# Phaser_Board.net
KiCad netlist of a schematic drawn in EAGLE
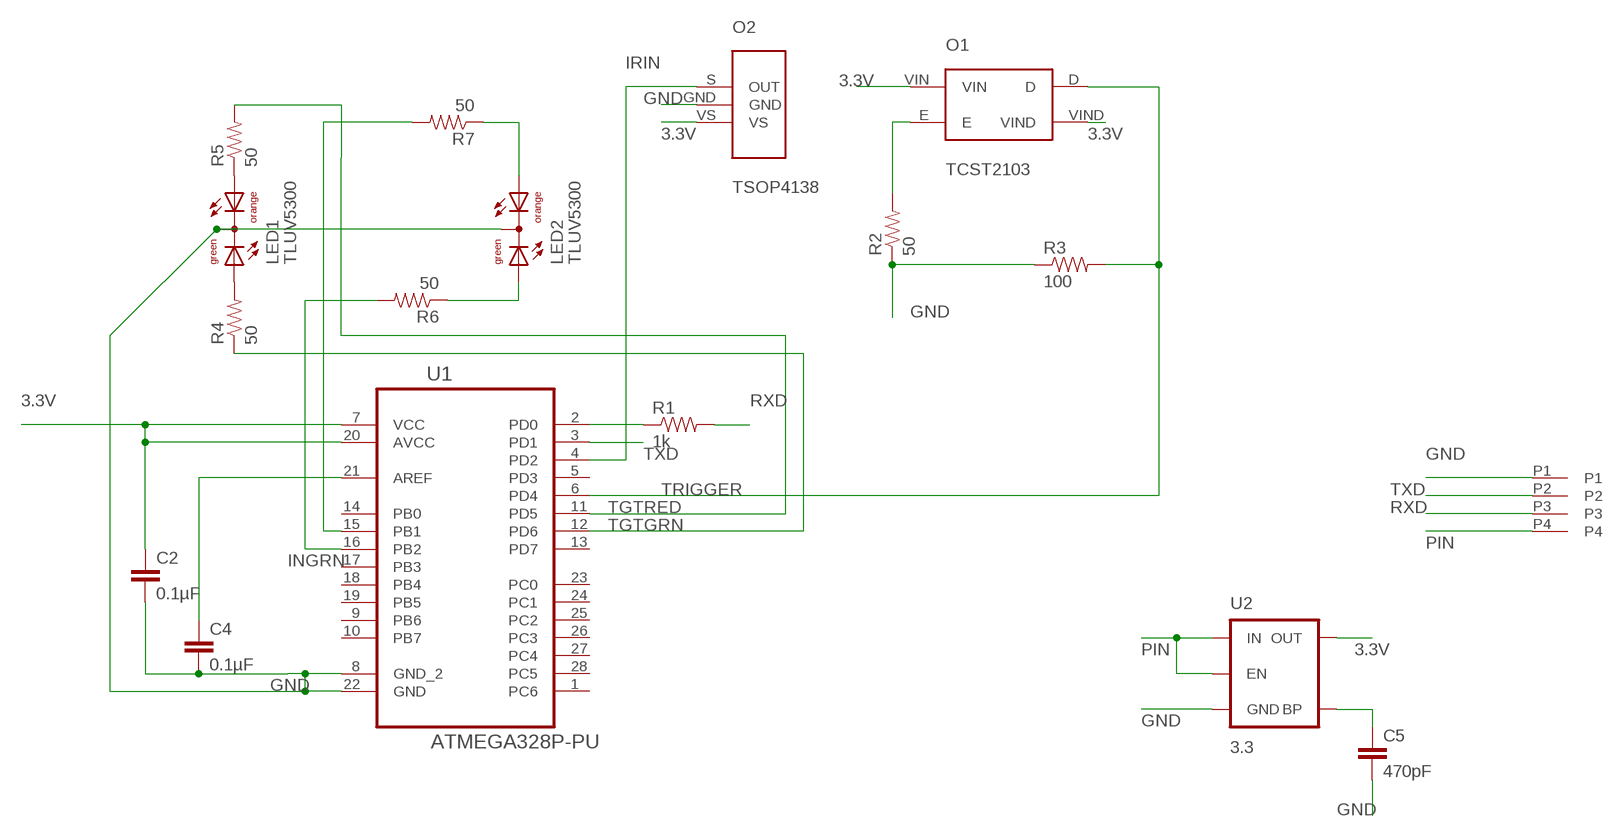
[diagram p0: schematic, sheet 1]

(export (version "E")
  (design (tool "Eeschema 10.0.6"))
  (components
    (comp (ref "C1")
      (value "KK396-4")
      (footprint "eagle-import:KK396-4")
      (libsource (lib "eagle-import") (part "KK396-4"))
    )
    (comp (ref "C2")
      (value "0.1µF")
      (footprint "eagle-import:1206")
      (libsource (lib "eagle-import") (part "CAP1206"))
    )
    (comp (ref "C4")
      (value "0.1µF")
      (footprint "eagle-import:1206")
      (libsource (lib "eagle-import") (part "CAP1206"))
    )
    (comp (ref "C5")
      (value "470pF")
      (footprint "eagle-import:1206")
      (libsource (lib "eagle-import") (part "CAP1206"))
    )
    (comp (ref "LED1")
      (value "TLUV5300")
      (footprint "eagle-import:TLUV5300")
      (libsource (lib "eagle-import") (part "TLUV5300"))
    )
    (comp (ref "LED2")
      (value "TLUV5300")
      (footprint "eagle-import:TLUV5300")
      (libsource (lib "eagle-import") (part "TLUV5300"))
    )
    (comp (ref "O1")
      (value "TCST2103")
      (footprint "eagle-import:TCST2103")
      (libsource (lib "eagle-import") (part "TCST2103"))
    )
    (comp (ref "O2")
      (value "TSOP4138")
      (footprint "eagle-import:TSOP4138")
      (libsource (lib "eagle-import") (part "TSOP4138"))
    )
    (comp (ref "R1")
      (value "1k")
      (footprint "eagle-import:0603-RES")
      (libsource (lib "eagle-import") (part "RESISTOR0603-RES"))
    )
    (comp (ref "R2")
      (value "50")
      (footprint "eagle-import:0603-RES")
      (libsource (lib "eagle-import") (part "RESISTOR0603-RES"))
    )
    (comp (ref "R3")
      (value "100")
      (footprint "eagle-import:0603-RES")
      (libsource (lib "eagle-import") (part "RESISTOR0603-RES"))
    )
    (comp (ref "R4")
      (value "50")
      (footprint "eagle-import:0603-RES")
      (libsource (lib "eagle-import") (part "RESISTOR0603-RES"))
    )
    (comp (ref "R5")
      (value "50")
      (footprint "eagle-import:0603-RES")
      (libsource (lib "eagle-import") (part "RESISTOR0603-RES"))
    )
    (comp (ref "R6")
      (value "50")
      (footprint "eagle-import:0603-RES")
      (libsource (lib "eagle-import") (part "RESISTOR0603-RES"))
    )
    (comp (ref "R7")
      (value "50")
      (footprint "eagle-import:0603-RES")
      (libsource (lib "eagle-import") (part "RESISTOR0603-RES"))
    )
    (comp (ref "U1")
      (value "ATMEGA328P-PU")
      (footprint "eagle-import:DIP254P762X457-28")
      (fields (field (name "SPICEPREFIX") "X"))
      (libsource (lib "eagle-import") (part "ATMEGA328P-PU"))
    )
    (comp (ref "U2")
      (value "3.3")
      (footprint "eagle-import:SOT23-5")
      (libsource (lib "eagle-import") (part "MIC52053.3V"))
    )
  )
  (nets
    (net (code "1") (name "/3.3V") (class "Default")
      (node (ref "C2") (pin "1") (pinfunction "1_1") (pintype "passive"))
      (node (ref "O1") (pin "VIN") (pinfunction "VIN_VIN") (pintype "bidirectional"))
      (node (ref "O1") (pin "VIND") (pinfunction "VIND_VIND") (pintype "bidirectional"))
      (node (ref "O2") (pin "VS") (pinfunction "VS_VS") (pintype "bidirectional"))
      (node (ref "U1") (pin "20") (pinfunction "AVCC_20") (pintype "power_in"))
      (node (ref "U1") (pin "7") (pinfunction "VCC_7") (pintype "power_in"))
      (node (ref "U2") (pin "5") (pinfunction "OUT_5") (pintype "passive"))
    )
    (net (code "2") (name "/GND") (class "Default")
      (node (ref "C1") (pin "P1") (pinfunction "P1_P1") (pintype "bidirectional"))
      (node (ref "C2") (pin "2") (pinfunction "2_2") (pintype "passive"))
      (node (ref "C4") (pin "2") (pinfunction "2_2") (pintype "passive"))
      (node (ref "C5") (pin "2") (pinfunction "2_2") (pintype "passive"))
      (node (ref "LED1") (pin "CC") (pinfunction "CC_CC") (pintype "passive"))
      (node (ref "LED2") (pin "CC") (pinfunction "CC_CC") (pintype "passive"))
      (node (ref "O2") (pin "GND") (pinfunction "GND_GND") (pintype "bidirectional"))
      (node (ref "R2") (pin "1") (pinfunction "1_1") (pintype "passive"))
      (node (ref "R3") (pin "1") (pinfunction "1_1") (pintype "passive"))
      (node (ref "U1") (pin "22") (pinfunction "GND_22") (pintype "passive"))
      (node (ref "U1") (pin "8") (pinfunction "GND_2_8") (pintype "passive"))
      (node (ref "U2") (pin "2") (pinfunction "GND_2") (pintype "input"))
    )
    (net (code "3") (name "/INGRN") (class "Default")
      (node (ref "R6") (pin "2") (pinfunction "2_2") (pintype "passive"))
      (node (ref "U1") (pin "16") (pinfunction "PB2_16") (pintype "bidirectional"))
    )
    (net (code "4") (name "/IRIN") (class "Default")
      (node (ref "O2") (pin "S") (pinfunction "OUT_S") (pintype "bidirectional"))
      (node (ref "U1") (pin "4") (pinfunction "PD2_4") (pintype "bidirectional"))
    )
    (net (code "5") (name "/PIN") (class "Default")
      (node (ref "C1") (pin "P4") (pinfunction "P4_P4") (pintype "bidirectional"))
      (node (ref "U2") (pin "1") (pinfunction "IN_1") (pintype "input"))
      (node (ref "U2") (pin "3") (pinfunction "EN_3") (pintype "input"))
    )
    (net (code "6") (name "/RXD") (class "Default")
      (node (ref "C1") (pin "P3") (pinfunction "P3_P3") (pintype "bidirectional"))
      (node (ref "R1") (pin "2") (pinfunction "2_2") (pintype "passive"))
    )
    (net (code "7") (name "/TGTGRN") (class "Default")
      (node (ref "R4") (pin "1") (pinfunction "1_1") (pintype "passive"))
      (node (ref "U1") (pin "12") (pinfunction "PD6_12") (pintype "bidirectional"))
    )
    (net (code "8") (name "/TGTRED") (class "Default")
      (node (ref "R5") (pin "2") (pinfunction "2_2") (pintype "passive"))
      (node (ref "U1") (pin "11") (pinfunction "PD5_11") (pintype "bidirectional"))
    )
    (net (code "9") (name "/TRIGGER") (class "Default")
      (node (ref "O1") (pin "D") (pinfunction "D_D") (pintype "bidirectional"))
      (node (ref "R3") (pin "2") (pinfunction "2_2") (pintype "passive"))
      (node (ref "U1") (pin "6") (pinfunction "PD4_6") (pintype "bidirectional"))
    )
    (net (code "10") (name "/TXD") (class "Default")
      (node (ref "C1") (pin "P2") (pinfunction "P2_P2") (pintype "bidirectional"))
      (node (ref "U1") (pin "3") (pinfunction "PD1_3") (pintype "bidirectional"))
    )
    (net (code "11") (name "Net-(LED1-PadAG)") (class "Default")
      (node (ref "LED1") (pin "AG") (pinfunction "AG_AG") (pintype "passive"))
      (node (ref "R4") (pin "2") (pinfunction "2_2") (pintype "passive"))
    )
    (net (code "12") (name "Net-(LED1-PadAO)") (class "Default")
      (node (ref "LED1") (pin "AO") (pinfunction "AO_AO") (pintype "passive"))
      (node (ref "R5") (pin "1") (pinfunction "1_1") (pintype "passive"))
    )
    (net (code "13") (name "Net-(LED2-PadAG)") (class "Default")
      (node (ref "LED2") (pin "AG") (pinfunction "AG_AG") (pintype "passive"))
      (node (ref "R6") (pin "1") (pinfunction "1_1") (pintype "passive"))
    )
    (net (code "14") (name "Net-(LED2-PadAO)") (class "Default")
      (node (ref "LED2") (pin "AO") (pinfunction "AO_AO") (pintype "passive"))
      (node (ref "R7") (pin "1") (pinfunction "1_1") (pintype "passive"))
    )
    (net (code "15") (name "Net-(O1-PadE)") (class "Default")
      (node (ref "O1") (pin "E") (pinfunction "E_E") (pintype "bidirectional"))
      (node (ref "R2") (pin "2") (pinfunction "2_2") (pintype "passive"))
    )
    (net (code "16") (name "Net-(U1-AREF)") (class "Default")
      (node (ref "C4") (pin "1") (pinfunction "1_1") (pintype "passive"))
      (node (ref "U1") (pin "21") (pinfunction "AREF_21") (pintype "input"))
    )
    (net (code "17") (name "Net-(U1-PB1)") (class "Default")
      (node (ref "R7") (pin "2") (pinfunction "2_2") (pintype "passive"))
      (node (ref "U1") (pin "15") (pinfunction "PB1_15") (pintype "bidirectional"))
    )
    (net (code "18") (name "Net-(U1-PD0)") (class "Default")
      (node (ref "R1") (pin "1") (pinfunction "1_1") (pintype "passive"))
      (node (ref "U1") (pin "2") (pinfunction "PD0_2") (pintype "bidirectional"))
    )
    (net (code "19") (name "Net-(U2-BP)") (class "Default")
      (node (ref "C5") (pin "1") (pinfunction "1_1") (pintype "passive"))
      (node (ref "U2") (pin "4") (pinfunction "BP_4") (pintype "input"))
    )
    (net (code "20") (name "unconnected-(U1-PB0-Pad14)") (class "Default")
      (node (ref "U1") (pin "14") (pinfunction "PB0_14") (pintype "bidirectional"))
    )
    (net (code "21") (name "unconnected-(U1-PB3-Pad17)") (class "Default")
      (node (ref "U1") (pin "17") (pinfunction "PB3_17") (pintype "bidirectional"))
    )
    (net (code "22") (name "unconnected-(U1-PB4-Pad18)") (class "Default")
      (node (ref "U1") (pin "18") (pinfunction "PB4_18") (pintype "bidirectional"))
    )
    (net (code "23") (name "unconnected-(U1-PB5-Pad19)") (class "Default")
      (node (ref "U1") (pin "19") (pinfunction "PB5_19") (pintype "bidirectional"))
    )
    (net (code "24") (name "unconnected-(U1-PB6-Pad9)") (class "Default")
      (node (ref "U1") (pin "9") (pinfunction "PB6_9") (pintype "bidirectional"))
    )
    (net (code "25") (name "unconnected-(U1-PB7-Pad10)") (class "Default")
      (node (ref "U1") (pin "10") (pinfunction "PB7_10") (pintype "bidirectional"))
    )
    (net (code "26") (name "unconnected-(U1-PC0-Pad23)") (class "Default")
      (node (ref "U1") (pin "23") (pinfunction "PC0_23") (pintype "bidirectional"))
    )
    (net (code "27") (name "unconnected-(U1-PC1-Pad24)") (class "Default")
      (node (ref "U1") (pin "24") (pinfunction "PC1_24") (pintype "bidirectional"))
    )
    (net (code "28") (name "unconnected-(U1-PC2-Pad25)") (class "Default")
      (node (ref "U1") (pin "25") (pinfunction "PC2_25") (pintype "bidirectional"))
    )
    (net (code "29") (name "unconnected-(U1-PC3-Pad26)") (class "Default")
      (node (ref "U1") (pin "26") (pinfunction "PC3_26") (pintype "bidirectional"))
    )
    (net (code "30") (name "unconnected-(U1-PC4-Pad27)") (class "Default")
      (node (ref "U1") (pin "27") (pinfunction "PC4_27") (pintype "bidirectional"))
    )
    (net (code "31") (name "unconnected-(U1-PC5-Pad28)") (class "Default")
      (node (ref "U1") (pin "28") (pinfunction "PC5_28") (pintype "bidirectional"))
    )
    (net (code "32") (name "unconnected-(U1-PC6-Pad1)") (class "Default")
      (node (ref "U1") (pin "1") (pinfunction "PC6_1") (pintype "bidirectional"))
    )
    (net (code "33") (name "unconnected-(U1-PD3-Pad5)") (class "Default")
      (node (ref "U1") (pin "5") (pinfunction "PD3_5") (pintype "bidirectional"))
    )
    (net (code "34") (name "unconnected-(U1-PD7-Pad13)") (class "Default")
      (node (ref "U1") (pin "13") (pinfunction "PD7_13") (pintype "bidirectional"))
    )
  )
)
